# Iron-Flybar-Main-PCB.net
KiCad netlist of a schematic drawn in EAGLE
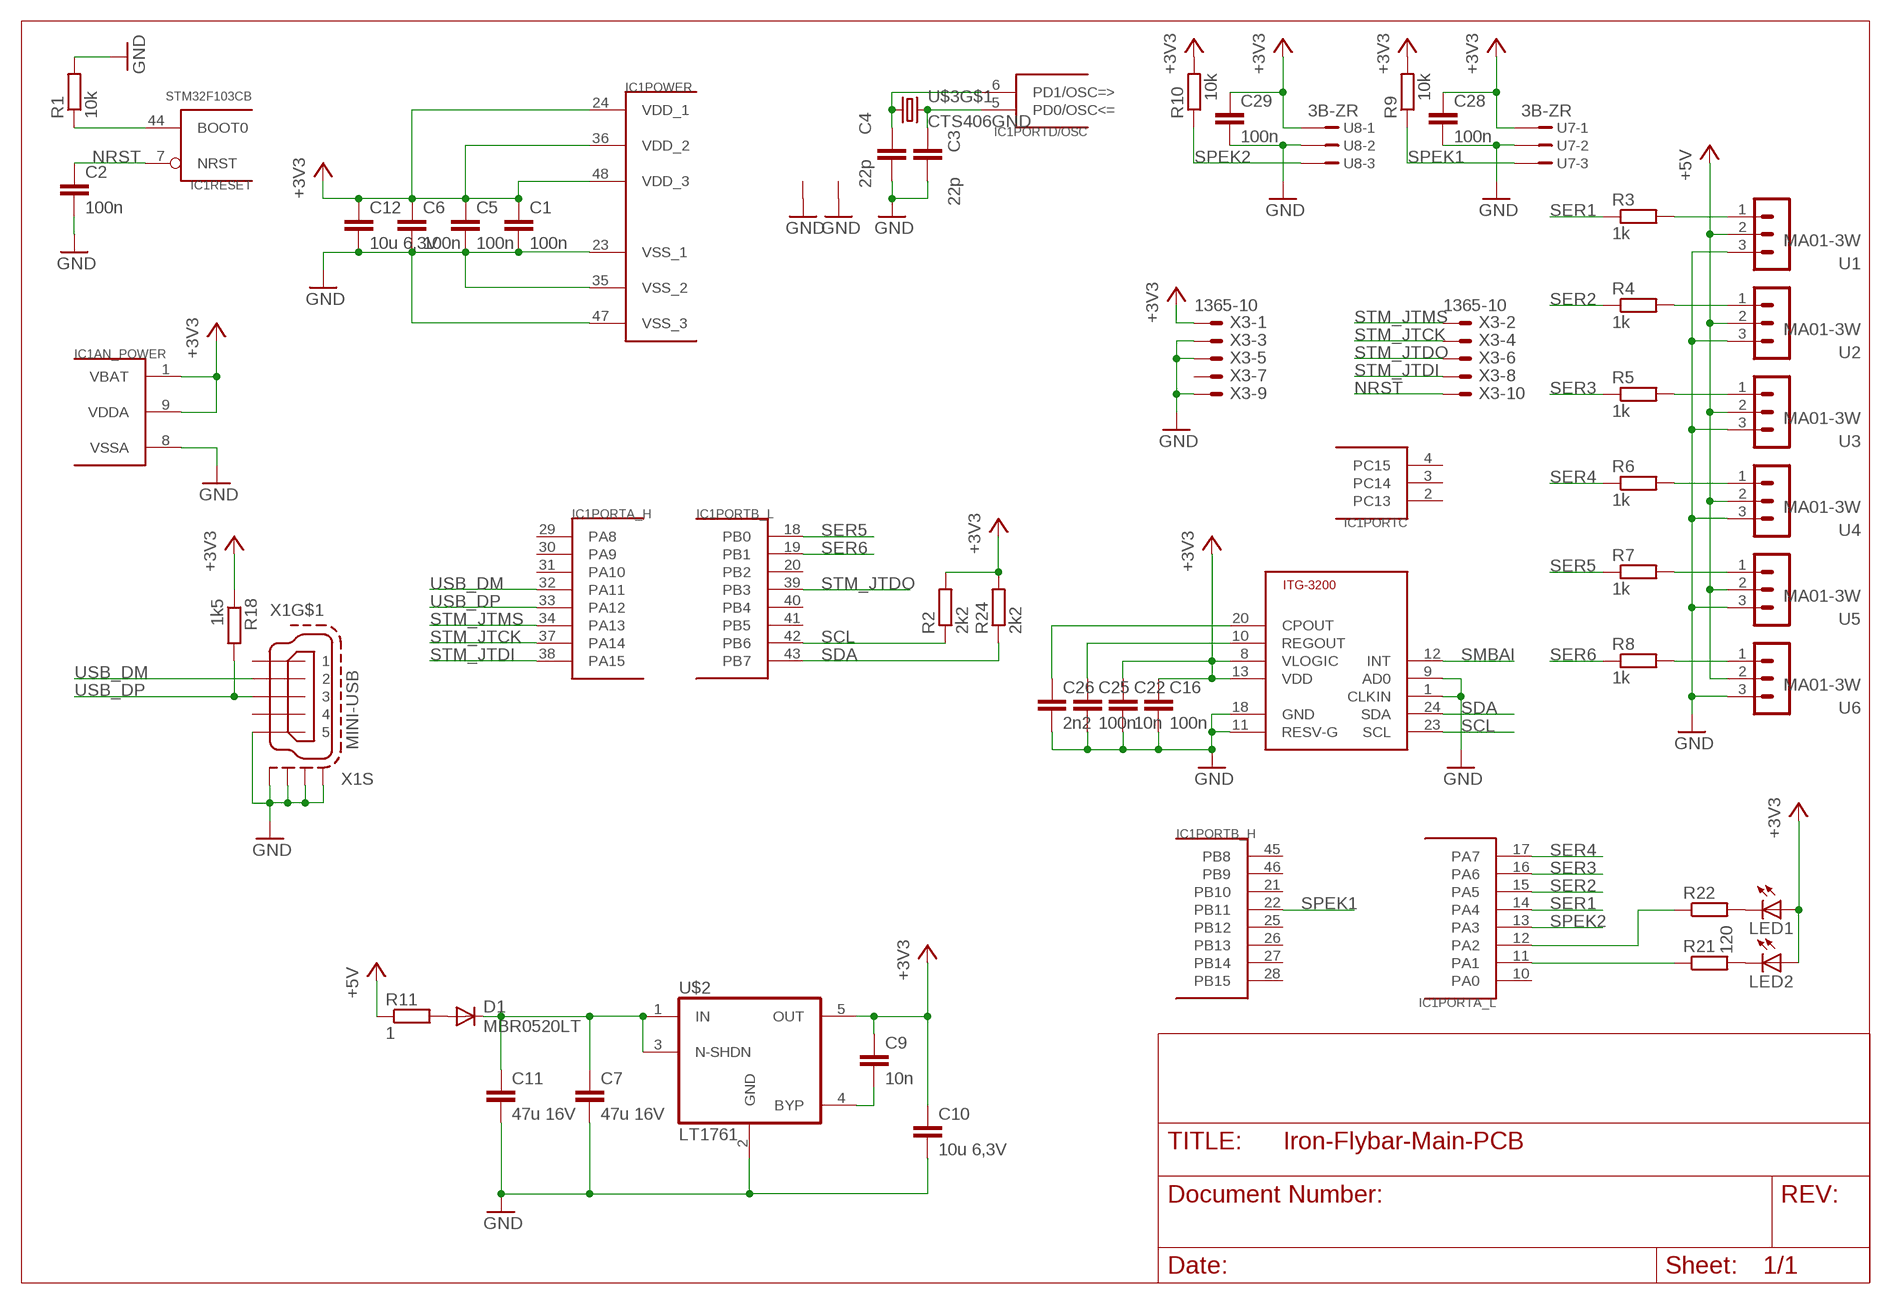
[diagram p0: schematic, sheet 1]

(export (version "E")
  (design (tool "Eeschema 10.0.6"))
  (components
    (comp (ref "C1")
      (value "100n")
      (footprint "eagle-import:C0603")
      (libsource (lib "eagle-import") (part "C-EUC0603"))
    )
    (comp (ref "C2")
      (value "100n")
      (footprint "eagle-import:C0603")
      (libsource (lib "eagle-import") (part "C-EUC0603"))
    )
    (comp (ref "C3")
      (value "22p")
      (footprint "eagle-import:C0603")
      (libsource (lib "eagle-import") (part "C-EUC0603"))
    )
    (comp (ref "C4")
      (value "22p")
      (footprint "eagle-import:C0603")
      (libsource (lib "eagle-import") (part "C-EUC0603"))
    )
    (comp (ref "C5")
      (value "100n")
      (footprint "eagle-import:C0603")
      (libsource (lib "eagle-import") (part "C-EUC0603"))
    )
    (comp (ref "C6")
      (value "100n")
      (footprint "eagle-import:C0603")
      (libsource (lib "eagle-import") (part "C-EUC0603"))
    )
    (comp (ref "C7")
      (value "47u 16V")
      (footprint "eagle-import:C1210K")
      (libsource (lib "eagle-import") (part "C-EUC1210K"))
    )
    (comp (ref "C9")
      (value "10n")
      (footprint "eagle-import:C0603K")
      (libsource (lib "eagle-import") (part "C-EUC0603K"))
    )
    (comp (ref "C10")
      (value "10u 6,3V")
      (footprint "eagle-import:C0603K")
      (libsource (lib "eagle-import") (part "C-EUC0603K"))
    )
    (comp (ref "C11")
      (value "47u 16V")
      (footprint "eagle-import:C1210K")
      (libsource (lib "eagle-import") (part "C-EUC1210K"))
    )
    (comp (ref "C12")
      (value "10u 6,3V")
      (footprint "eagle-import:C0603K")
      (libsource (lib "eagle-import") (part "C-EUC0603K"))
    )
    (comp (ref "C16")
      (value "100n")
      (footprint "eagle-import:C0603")
      (libsource (lib "eagle-import") (part "C-EUC0603"))
    )
    (comp (ref "C22")
      (value "10n")
      (footprint "eagle-import:C0603")
      (libsource (lib "eagle-import") (part "C-EUC0603"))
    )
    (comp (ref "C25")
      (value "100n")
      (footprint "eagle-import:C0603")
      (libsource (lib "eagle-import") (part "C-EUC0603"))
    )
    (comp (ref "C26")
      (value "2n2")
      (footprint "eagle-import:C0603")
      (libsource (lib "eagle-import") (part "C-EUC0603"))
    )
    (comp (ref "C28")
      (value "100n")
      (footprint "eagle-import:C0603")
      (libsource (lib "eagle-import") (part "C-EUC0603"))
    )
    (comp (ref "C29")
      (value "100n")
      (footprint "eagle-import:C0603")
      (libsource (lib "eagle-import") (part "C-EUC0603"))
    )
    (comp (ref "D1")
      (value "MBR0520LT")
      (footprint "eagle-import:SOD123")
      (libsource (lib "eagle-import") (part "MBR0520LT"))
    )
    (comp (ref "IC1")
      (value "STM32F103CB")
      (footprint "eagle-import:TQFP48")
      (libsource (lib "eagle-import") (part "STM32F10XCXT6"))
    )
    (comp (ref "LED1")
      (value "LEDCHIP-LED0603")
      (footprint "eagle-import:CHIP-LED0603")
      (libsource (lib "eagle-import") (part "LEDCHIP-LED0603"))
    )
    (comp (ref "LED2")
      (value "LEDCHIP-LED0603")
      (footprint "eagle-import:CHIP-LED0603")
      (libsource (lib "eagle-import") (part "LEDCHIP-LED0603"))
    )
    (comp (ref "R1")
      (value "10k")
      (footprint "eagle-import:R0603")
      (libsource (lib "eagle-import") (part "R-EU_R0603"))
    )
    (comp (ref "R2")
      (value "2k2")
      (footprint "eagle-import:R0603")
      (libsource (lib "eagle-import") (part "R-EU_R0603"))
    )
    (comp (ref "R3")
      (value "1k")
      (footprint "eagle-import:R0603")
      (libsource (lib "eagle-import") (part "R-EU_R0603"))
    )
    (comp (ref "R4")
      (value "1k")
      (footprint "eagle-import:R0603")
      (libsource (lib "eagle-import") (part "R-EU_R0603"))
    )
    (comp (ref "R5")
      (value "1k")
      (footprint "eagle-import:R0603")
      (libsource (lib "eagle-import") (part "R-EU_R0603"))
    )
    (comp (ref "R6")
      (value "1k")
      (footprint "eagle-import:R0603")
      (libsource (lib "eagle-import") (part "R-EU_R0603"))
    )
    (comp (ref "R7")
      (value "1k")
      (footprint "eagle-import:R0603")
      (libsource (lib "eagle-import") (part "R-EU_R0603"))
    )
    (comp (ref "R8")
      (value "1k")
      (footprint "eagle-import:R0603")
      (libsource (lib "eagle-import") (part "R-EU_R0603"))
    )
    (comp (ref "R9")
      (value "10k")
      (footprint "eagle-import:R0603")
      (libsource (lib "eagle-import") (part "R-EU_R0603"))
    )
    (comp (ref "R10")
      (value "10k")
      (footprint "eagle-import:R0603")
      (libsource (lib "eagle-import") (part "R-EU_R0603"))
    )
    (comp (ref "R11")
      (value "1")
      (footprint "eagle-import:R0603")
      (libsource (lib "eagle-import") (part "R-EU_R0603"))
    )
    (comp (ref "R18")
      (value "1k5")
      (footprint "eagle-import:R0603")
      (libsource (lib "eagle-import") (part "R-EU_R0603"))
    )
    (comp (ref "R21")
      (value "120")
      (footprint "eagle-import:R0603")
      (libsource (lib "eagle-import") (part "R-EU_R0603"))
    )
    (comp (ref "R22")
      (value "120")
      (footprint "eagle-import:R0603")
      (libsource (lib "eagle-import") (part "R-EU_R0603"))
    )
    (comp (ref "R24")
      (value "2k2")
      (footprint "eagle-import:R0603")
      (libsource (lib "eagle-import") (part "R-EU_R0603"))
    )
    (comp (ref "U$1")
      (value "ITG-3200")
      (footprint "eagle-import:ITG-3200")
      (libsource (lib "eagle-import") (part "ITG-3200"))
    )
    (comp (ref "U$2")
      (value "LT1761")
      (footprint "eagle-import:TSOT23-5")
      (libsource (lib "eagle-import") (part "LT1761"))
    )
    (comp (ref "U$3")
      (value "CTS406GND")
      (footprint "eagle-import:CTS406")
      (libsource (lib "eagle-import") (part "CTS406GND"))
    )
    (comp (ref "U1")
      (value "MA01-3W")
      (footprint "eagle-import:MA01-3W")
      (libsource (lib "eagle-import") (part "MA01-3W"))
    )
    (comp (ref "U2")
      (value "MA01-3W")
      (footprint "eagle-import:MA01-3W")
      (libsource (lib "eagle-import") (part "MA01-3W"))
    )
    (comp (ref "U3")
      (value "MA01-3W")
      (footprint "eagle-import:MA01-3W")
      (libsource (lib "eagle-import") (part "MA01-3W"))
    )
    (comp (ref "U4")
      (value "MA01-3W")
      (footprint "eagle-import:MA01-3W")
      (libsource (lib "eagle-import") (part "MA01-3W"))
    )
    (comp (ref "U5")
      (value "MA01-3W")
      (footprint "eagle-import:MA01-3W")
      (libsource (lib "eagle-import") (part "MA01-3W"))
    )
    (comp (ref "U6")
      (value "MA01-3W")
      (footprint "eagle-import:MA01-3W")
      (libsource (lib "eagle-import") (part "MA01-3W"))
    )
    (comp (ref "U7")
      (value "3B-ZR")
      (footprint "eagle-import:S3B-ZR")
      (libsource (lib "eagle-import") (part "?3B-ZR"))
    )
    (comp (ref "U8")
      (value "3B-ZR")
      (footprint "eagle-import:S3B-ZR")
      (libsource (lib "eagle-import") (part "?3B-ZR"))
    )
    (comp (ref "X1")
      (value "MINI-USB")
      (footprint "eagle-import:32005-301")
      (libsource (lib "eagle-import") (part "MINI-USB-SCHIELD-32005-301"))
    )
    (comp (ref "X3")
      (value "1365-10")
      (footprint "eagle-import:1365-10")
      (libsource (lib "eagle-import") (part "1365-10"))
    )
  )
  (nets
    (net (code "1") (name "+3V3") (class "Default")
      (node (ref "C1") (pin "1") (pinfunction "1_1") (pintype "passive"))
      (node (ref "C10") (pin "1") (pinfunction "1_1") (pintype "passive"))
      (node (ref "C12") (pin "1") (pinfunction "1_1") (pintype "passive"))
      (node (ref "C16") (pin "1") (pinfunction "1_1") (pintype "passive"))
      (node (ref "C22") (pin "1") (pinfunction "1_1") (pintype "passive"))
      (node (ref "C28") (pin "1") (pinfunction "1_1") (pintype "passive"))
      (node (ref "C29") (pin "1") (pinfunction "1_1") (pintype "passive"))
      (node (ref "C5") (pin "1") (pinfunction "1_1") (pintype "passive"))
      (node (ref "C6") (pin "1") (pinfunction "1_1") (pintype "passive"))
      (node (ref "C9") (pin "1") (pinfunction "1_1") (pintype "passive"))
      (node (ref "IC1") (pin "1") (pinfunction "VBAT_1") (pintype "power_in"))
      (node (ref "IC1") (pin "24") (pinfunction "VDD_1_24") (pintype "power_in"))
      (node (ref "IC1") (pin "36") (pinfunction "VDD_2_36") (pintype "power_in"))
      (node (ref "IC1") (pin "48") (pinfunction "VDD_3_48") (pintype "power_in"))
      (node (ref "IC1") (pin "9") (pinfunction "VDDA_9") (pintype "power_in"))
      (node (ref "LED1") (pin "A") (pinfunction "A_A") (pintype "passive"))
      (node (ref "LED2") (pin "A") (pinfunction "A_A") (pintype "passive"))
      (node (ref "R10") (pin "2") (pinfunction "2_2") (pintype "passive"))
      (node (ref "R18") (pin "1") (pinfunction "1_1") (pintype "passive"))
      (node (ref "R2") (pin "2") (pinfunction "2_2") (pintype "passive"))
      (node (ref "R24") (pin "2") (pinfunction "2_2") (pintype "passive"))
      (node (ref "R9") (pin "2") (pinfunction "2_2") (pintype "passive"))
      (node (ref "U$1") (pin "13") (pinfunction "VDD_13") (pintype "output"))
      (node (ref "U$1") (pin "8") (pinfunction "VLOGIC_8") (pintype "output"))
      (node (ref "U$2") (pin "5") (pinfunction "OUT_5") (pintype "output"))
      (node (ref "U7") (pin "1") (pinfunction "1_1") (pintype "passive"))
      (node (ref "U8") (pin "1") (pinfunction "1_1") (pintype "passive"))
      (node (ref "X3") (pin "1") (pinfunction "S_1") (pintype "passive"))
    )
    (net (code "2") (name "+5V") (class "Default")
      (node (ref "R11") (pin "1") (pinfunction "1_1") (pintype "passive"))
      (node (ref "U1") (pin "2") (pinfunction "2_2") (pintype "passive"))
      (node (ref "U2") (pin "2") (pinfunction "2_2") (pintype "passive"))
      (node (ref "U3") (pin "2") (pinfunction "2_2") (pintype "passive"))
      (node (ref "U4") (pin "2") (pinfunction "2_2") (pintype "passive"))
      (node (ref "U5") (pin "2") (pinfunction "2_2") (pintype "passive"))
      (node (ref "U6") (pin "2") (pinfunction "2_2") (pintype "passive"))
    )
    (net (code "3") (name "/NRST") (class "Default")
      (node (ref "C2") (pin "1") (pinfunction "1_1") (pintype "passive"))
      (node (ref "IC1") (pin "7") (pinfunction "NRST_7") (pintype "input"))
      (node (ref "X3") (pin "10") (pinfunction "S_10") (pintype "passive"))
    )
    (net (code "4") (name "/SCL") (class "Default")
      (node (ref "IC1") (pin "42") (pinfunction "PB6_42") (pintype "bidirectional"))
      (node (ref "R2") (pin "1") (pinfunction "1_1") (pintype "passive"))
      (node (ref "U$1") (pin "23") (pinfunction "SCL_23") (pintype "input"))
    )
    (net (code "5") (name "/SDA") (class "Default")
      (node (ref "IC1") (pin "43") (pinfunction "PB7_43") (pintype "bidirectional"))
      (node (ref "R24") (pin "1") (pinfunction "1_1") (pintype "passive"))
      (node (ref "U$1") (pin "24") (pinfunction "SDA_24") (pintype "bidirectional"))
    )
    (net (code "6") (name "/SER1") (class "Default")
      (node (ref "IC1") (pin "14") (pinfunction "PA4_14") (pintype "bidirectional"))
      (node (ref "R3") (pin "1") (pinfunction "1_1") (pintype "passive"))
    )
    (net (code "7") (name "/SER2") (class "Default")
      (node (ref "IC1") (pin "15") (pinfunction "PA5_15") (pintype "bidirectional"))
      (node (ref "R4") (pin "1") (pinfunction "1_1") (pintype "passive"))
    )
    (net (code "8") (name "/SER3") (class "Default")
      (node (ref "IC1") (pin "16") (pinfunction "PA6_16") (pintype "bidirectional"))
      (node (ref "R5") (pin "1") (pinfunction "1_1") (pintype "passive"))
    )
    (net (code "9") (name "/SER4") (class "Default")
      (node (ref "IC1") (pin "17") (pinfunction "PA7_17") (pintype "bidirectional"))
      (node (ref "R6") (pin "1") (pinfunction "1_1") (pintype "passive"))
    )
    (net (code "10") (name "/SER5") (class "Default")
      (node (ref "IC1") (pin "18") (pinfunction "PB0_18") (pintype "bidirectional"))
      (node (ref "R7") (pin "1") (pinfunction "1_1") (pintype "passive"))
    )
    (net (code "11") (name "/SER6") (class "Default")
      (node (ref "IC1") (pin "19") (pinfunction "PB1_19") (pintype "bidirectional"))
      (node (ref "R8") (pin "1") (pinfunction "1_1") (pintype "passive"))
    )
    (net (code "12") (name "/SMBAI") (class "Default")
      (node (ref "U$1") (pin "12") (pinfunction "INT_12") (pintype "output"))
    )
    (net (code "13") (name "/SPEK1") (class "Default")
      (node (ref "IC1") (pin "22") (pinfunction "PB11_22") (pintype "bidirectional"))
      (node (ref "R9") (pin "1") (pinfunction "1_1") (pintype "passive"))
      (node (ref "U7") (pin "3") (pinfunction "1_3") (pintype "passive"))
    )
    (net (code "14") (name "/SPEK2") (class "Default")
      (node (ref "IC1") (pin "13") (pinfunction "PA3_13") (pintype "bidirectional"))
      (node (ref "R10") (pin "1") (pinfunction "1_1") (pintype "passive"))
      (node (ref "U8") (pin "3") (pinfunction "1_3") (pintype "passive"))
    )
    (net (code "15") (name "/STM_JTCK") (class "Default")
      (node (ref "IC1") (pin "37") (pinfunction "PA14_37") (pintype "bidirectional"))
      (node (ref "X3") (pin "4") (pinfunction "S_4") (pintype "passive"))
    )
    (net (code "16") (name "/STM_JTDI") (class "Default")
      (node (ref "IC1") (pin "38") (pinfunction "PA15_38") (pintype "bidirectional"))
      (node (ref "X3") (pin "8") (pinfunction "S_8") (pintype "passive"))
    )
    (net (code "17") (name "/STM_JTDO") (class "Default")
      (node (ref "IC1") (pin "39") (pinfunction "PB3_39") (pintype "bidirectional"))
      (node (ref "X3") (pin "6") (pinfunction "S_6") (pintype "passive"))
    )
    (net (code "18") (name "/STM_JTMS") (class "Default")
      (node (ref "IC1") (pin "34") (pinfunction "PA13_34") (pintype "bidirectional"))
      (node (ref "X3") (pin "2") (pinfunction "S_2") (pintype "passive"))
    )
    (net (code "19") (name "/USB_DM") (class "Default")
      (node (ref "IC1") (pin "32") (pinfunction "PA11_32") (pintype "bidirectional"))
      (node (ref "X1") (pin "2") (pinfunction "2_2") (pintype "passive"))
    )
    (net (code "20") (name "/USB_DP") (class "Default")
      (node (ref "IC1") (pin "33") (pinfunction "PA12_33") (pintype "bidirectional"))
      (node (ref "R18") (pin "2") (pinfunction "2_2") (pintype "passive"))
      (node (ref "X1") (pin "3") (pinfunction "3_3") (pintype "passive"))
    )
    (net (code "21") (name "GND") (class "Default")
      (node (ref "C1") (pin "2") (pinfunction "2_2") (pintype "passive"))
      (node (ref "C10") (pin "2") (pinfunction "2_2") (pintype "passive"))
      (node (ref "C11") (pin "2") (pinfunction "2_2") (pintype "passive"))
      (node (ref "C12") (pin "2") (pinfunction "2_2") (pintype "passive"))
      (node (ref "C16") (pin "2") (pinfunction "2_2") (pintype "passive"))
      (node (ref "C2") (pin "2") (pinfunction "2_2") (pintype "passive"))
      (node (ref "C22") (pin "2") (pinfunction "2_2") (pintype "passive"))
      (node (ref "C25") (pin "2") (pinfunction "2_2") (pintype "passive"))
      (node (ref "C26") (pin "2") (pinfunction "2_2") (pintype "passive"))
      (node (ref "C28") (pin "2") (pinfunction "2_2") (pintype "passive"))
      (node (ref "C29") (pin "2") (pinfunction "2_2") (pintype "passive"))
      (node (ref "C3") (pin "2") (pinfunction "2_2") (pintype "passive"))
      (node (ref "C4") (pin "2") (pinfunction "2_2") (pintype "passive"))
      (node (ref "C5") (pin "2") (pinfunction "2_2") (pintype "passive"))
      (node (ref "C6") (pin "2") (pinfunction "2_2") (pintype "passive"))
      (node (ref "C7") (pin "2") (pinfunction "2_2") (pintype "passive"))
      (node (ref "IC1") (pin "23") (pinfunction "VSS_1_23") (pintype "power_in"))
      (node (ref "IC1") (pin "35") (pinfunction "VSS_2_35") (pintype "power_in"))
      (node (ref "IC1") (pin "47") (pinfunction "VSS_3_47") (pintype "power_in"))
      (node (ref "IC1") (pin "8") (pinfunction "VSSA_8") (pintype "power_in"))
      (node (ref "R1") (pin "2") (pinfunction "2_2") (pintype "passive"))
      (node (ref "U$1") (pin "1") (pinfunction "CLKIN_1") (pintype "input"))
      (node (ref "U$1") (pin "11") (pinfunction "RESV-G_11") (pintype "power_in"))
      (node (ref "U$1") (pin "18") (pinfunction "GND_18") (pintype "power_in"))
      (node (ref "U$1") (pin "9") (pinfunction "AD0_9") (pintype "input"))
      (node (ref "U$2") (pin "2") (pinfunction "GND_2") (pintype "power_in"))
      (node (ref "U$3") (pin "2") (pinfunction "GND_2") (pintype "power_in"))
      (node (ref "U$3") (pin "4") (pinfunction "GND_4") (pintype "power_in"))
      (node (ref "U1") (pin "3") (pinfunction "3_3") (pintype "passive"))
      (node (ref "U2") (pin "3") (pinfunction "3_3") (pintype "passive"))
      (node (ref "U3") (pin "3") (pinfunction "3_3") (pintype "passive"))
      (node (ref "U4") (pin "3") (pinfunction "3_3") (pintype "passive"))
      (node (ref "U5") (pin "3") (pinfunction "3_3") (pintype "passive"))
      (node (ref "U6") (pin "3") (pinfunction "3_3") (pintype "passive"))
      (node (ref "U7") (pin "2") (pinfunction "1_2") (pintype "passive"))
      (node (ref "U8") (pin "2") (pinfunction "1_2") (pintype "passive"))
      (node (ref "X1") (pin "5") (pinfunction "5_5") (pintype "passive"))
      (node (ref "X1") (pin "M1") (pinfunction "S1_M1") (pintype "passive"))
      (node (ref "X1") (pin "M2") (pinfunction "S2_M2") (pintype "passive"))
      (node (ref "X1") (pin "M3") (pinfunction "S3_M3") (pintype "passive"))
      (node (ref "X1") (pin "M4") (pinfunction "S4_M4") (pintype "passive"))
      (node (ref "X3") (pin "3") (pinfunction "S_3") (pintype "passive"))
      (node (ref "X3") (pin "5") (pinfunction "S_5") (pintype "passive"))
      (node (ref "X3") (pin "9") (pinfunction "S_9") (pintype "passive"))
    )
    (net (code "22") (name "Net-(D1-PadA)") (class "Default")
      (node (ref "D1") (pin "A") (pinfunction "A_A") (pintype "passive"))
      (node (ref "R11") (pin "2") (pinfunction "2_2") (pintype "passive"))
    )
    (net (code "23") (name "Net-(IC1C-PA1)") (class "Default")
      (node (ref "IC1") (pin "11") (pinfunction "PA1_11") (pintype "bidirectional"))
      (node (ref "R21") (pin "1") (pinfunction "1_1") (pintype "passive"))
    )
    (net (code "24") (name "Net-(IC1C-PA2)") (class "Default")
      (node (ref "IC1") (pin "12") (pinfunction "PA2_12") (pintype "bidirectional"))
      (node (ref "R22") (pin "1") (pinfunction "1_1") (pintype "passive"))
    )
    (net (code "25") (name "Net-(IC1G-PD0{slash}OSC<=)") (class "Default")
      (node (ref "C3") (pin "1") (pinfunction "1_1") (pintype "passive"))
      (node (ref "IC1") (pin "5") (pinfunction "PD0/OSC<=_5") (pintype "bidirectional"))
      (node (ref "U$3") (pin "3") (pinfunction "2_3") (pintype "passive"))
    )
    (net (code "26") (name "Net-(IC1G-PD1{slash}OSC=>)") (class "Default")
      (node (ref "C4") (pin "1") (pinfunction "1_1") (pintype "passive"))
      (node (ref "IC1") (pin "6") (pinfunction "PD1/OSC=>_6") (pintype "bidirectional"))
      (node (ref "U$3") (pin "1") (pinfunction "1_1") (pintype "passive"))
    )
    (net (code "27") (name "Net-(IC1I-BOOT0)") (class "Default")
      (node (ref "IC1") (pin "44") (pinfunction "BOOT0_44") (pintype "input"))
      (node (ref "R1") (pin "1") (pinfunction "1_1") (pintype "passive"))
    )
    (net (code "28") (name "Net-(LED1-PadC)") (class "Default")
      (node (ref "LED1") (pin "C") (pinfunction "C_C") (pintype "passive"))
      (node (ref "R22") (pin "2") (pinfunction "2_2") (pintype "passive"))
    )
    (net (code "29") (name "Net-(LED2-PadC)") (class "Default")
      (node (ref "LED2") (pin "C") (pinfunction "C_C") (pintype "passive"))
      (node (ref "R21") (pin "2") (pinfunction "2_2") (pintype "passive"))
    )
    (net (code "30") (name "Net-(R3-Pad2)") (class "Default")
      (node (ref "R3") (pin "2") (pinfunction "2_2") (pintype "passive"))
      (node (ref "U1") (pin "1") (pinfunction "1_1") (pintype "passive"))
    )
    (net (code "31") (name "Net-(R4-Pad2)") (class "Default")
      (node (ref "R4") (pin "2") (pinfunction "2_2") (pintype "passive"))
      (node (ref "U2") (pin "1") (pinfunction "1_1") (pintype "passive"))
    )
    (net (code "32") (name "Net-(R5-Pad2)") (class "Default")
      (node (ref "R5") (pin "2") (pinfunction "2_2") (pintype "passive"))
      (node (ref "U3") (pin "1") (pinfunction "1_1") (pintype "passive"))
    )
    (net (code "33") (name "Net-(R6-Pad2)") (class "Default")
      (node (ref "R6") (pin "2") (pinfunction "2_2") (pintype "passive"))
      (node (ref "U4") (pin "1") (pinfunction "1_1") (pintype "passive"))
    )
    (net (code "34") (name "Net-(R7-Pad2)") (class "Default")
      (node (ref "R7") (pin "2") (pinfunction "2_2") (pintype "passive"))
      (node (ref "U5") (pin "1") (pinfunction "1_1") (pintype "passive"))
    )
    (net (code "35") (name "Net-(R8-Pad2)") (class "Default")
      (node (ref "R8") (pin "2") (pinfunction "2_2") (pintype "passive"))
      (node (ref "U6") (pin "1") (pinfunction "1_1") (pintype "passive"))
    )
    (net (code "36") (name "Net-(U$1-CPOUT)") (class "Default")
      (node (ref "C26") (pin "1") (pinfunction "1_1") (pintype "passive"))
      (node (ref "U$1") (pin "20") (pinfunction "CPOUT_20") (pintype "bidirectional"))
    )
    (net (code "37") (name "Net-(U$1-REGOUT)") (class "Default")
      (node (ref "C25") (pin "1") (pinfunction "1_1") (pintype "passive"))
      (node (ref "U$1") (pin "10") (pinfunction "REGOUT_10") (pintype "bidirectional"))
    )
    (net (code "38") (name "Net-(U$2-BYP)") (class "Default")
      (node (ref "C9") (pin "2") (pinfunction "2_2") (pintype "passive"))
      (node (ref "U$2") (pin "4") (pinfunction "BYP_4") (pintype "output"))
    )
    (net (code "39") (name "Net-(U$2-IN)") (class "Default")
      (node (ref "C11") (pin "1") (pinfunction "1_1") (pintype "passive"))
      (node (ref "C7") (pin "1") (pinfunction "1_1") (pintype "passive"))
      (node (ref "D1") (pin "C") (pinfunction "C_C") (pintype "passive"))
      (node (ref "U$2") (pin "1") (pinfunction "IN_1") (pintype "input"))
      (node (ref "U$2") (pin "3") (pinfunction "N-SHDN_3") (pintype "input"))
    )
    (net (code "40") (name "unconnected-(IC1B-PA8-Pad29)") (class "Default")
      (node (ref "IC1") (pin "29") (pinfunction "PA8_29") (pintype "bidirectional"))
    )
    (net (code "41") (name "unconnected-(IC1B-PA9-Pad30)") (class "Default")
      (node (ref "IC1") (pin "30") (pinfunction "PA9_30") (pintype "bidirectional"))
    )
    (net (code "42") (name "unconnected-(IC1B-PA10-Pad31)") (class "Default")
      (node (ref "IC1") (pin "31") (pinfunction "PA10_31") (pintype "bidirectional"))
    )
    (net (code "43") (name "unconnected-(IC1C-PA0-Pad10)") (class "Default")
      (node (ref "IC1") (pin "10") (pinfunction "PA0_10") (pintype "bidirectional"))
    )
    (net (code "44") (name "unconnected-(IC1D-PB8-Pad45)") (class "Default")
      (node (ref "IC1") (pin "45") (pinfunction "PB8_45") (pintype "bidirectional"))
    )
    (net (code "45") (name "unconnected-(IC1D-PB9-Pad46)") (class "Default")
      (node (ref "IC1") (pin "46") (pinfunction "PB9_46") (pintype "bidirectional"))
    )
    (net (code "46") (name "unconnected-(IC1D-PB10-Pad21)") (class "Default")
      (node (ref "IC1") (pin "21") (pinfunction "PB10_21") (pintype "bidirectional"))
    )
    (net (code "47") (name "unconnected-(IC1D-PB12-Pad25)") (class "Default")
      (node (ref "IC1") (pin "25") (pinfunction "PB12_25") (pintype "bidirectional"))
    )
    (net (code "48") (name "unconnected-(IC1D-PB13-Pad26)") (class "Default")
      (node (ref "IC1") (pin "26") (pinfunction "PB13_26") (pintype "bidirectional"))
    )
    (net (code "49") (name "unconnected-(IC1D-PB14-Pad27)") (class "Default")
      (node (ref "IC1") (pin "27") (pinfunction "PB14_27") (pintype "bidirectional"))
    )
    (net (code "50") (name "unconnected-(IC1D-PB15-Pad28)") (class "Default")
      (node (ref "IC1") (pin "28") (pinfunction "PB15_28") (pintype "bidirectional"))
    )
    (net (code "51") (name "unconnected-(IC1E-PB2-Pad20)") (class "Default")
      (node (ref "IC1") (pin "20") (pinfunction "PB2_20") (pintype "bidirectional"))
    )
    (net (code "52") (name "unconnected-(IC1E-PB4-Pad40)") (class "Default")
      (node (ref "IC1") (pin "40") (pinfunction "PB4_40") (pintype "bidirectional"))
    )
    (net (code "53") (name "unconnected-(IC1E-PB5-Pad41)") (class "Default")
      (node (ref "IC1") (pin "41") (pinfunction "PB5_41") (pintype "bidirectional"))
    )
    (net (code "54") (name "unconnected-(IC1F-PC13-Pad2)") (class "Default")
      (node (ref "IC1") (pin "2") (pinfunction "PC13_2") (pintype "bidirectional"))
    )
    (net (code "55") (name "unconnected-(IC1F-PC14-Pad3)") (class "Default")
      (node (ref "IC1") (pin "3") (pinfunction "PC14_3") (pintype "bidirectional"))
    )
    (net (code "56") (name "unconnected-(IC1F-PC15-Pad4)") (class "Default")
      (node (ref "IC1") (pin "4") (pinfunction "PC15_4") (pintype "bidirectional"))
    )
    (net (code "57") (name "unconnected-(X1-Pad1)") (class "Default")
      (node (ref "X1") (pin "1") (pinfunction "1_1") (pintype "passive"))
    )
    (net (code "58") (name "unconnected-(X1-Pad4)") (class "Default")
      (node (ref "X1") (pin "4") (pinfunction "4_4") (pintype "passive"))
    )
    (net (code "59") (name "unconnected-(X3H-S-Pad7)") (class "Default")
      (node (ref "X3") (pin "7") (pinfunction "S_7") (pintype "passive"))
    )
  )
)
